# Driver.net
KiCad netlist of a schematic drawn in Altium Designer
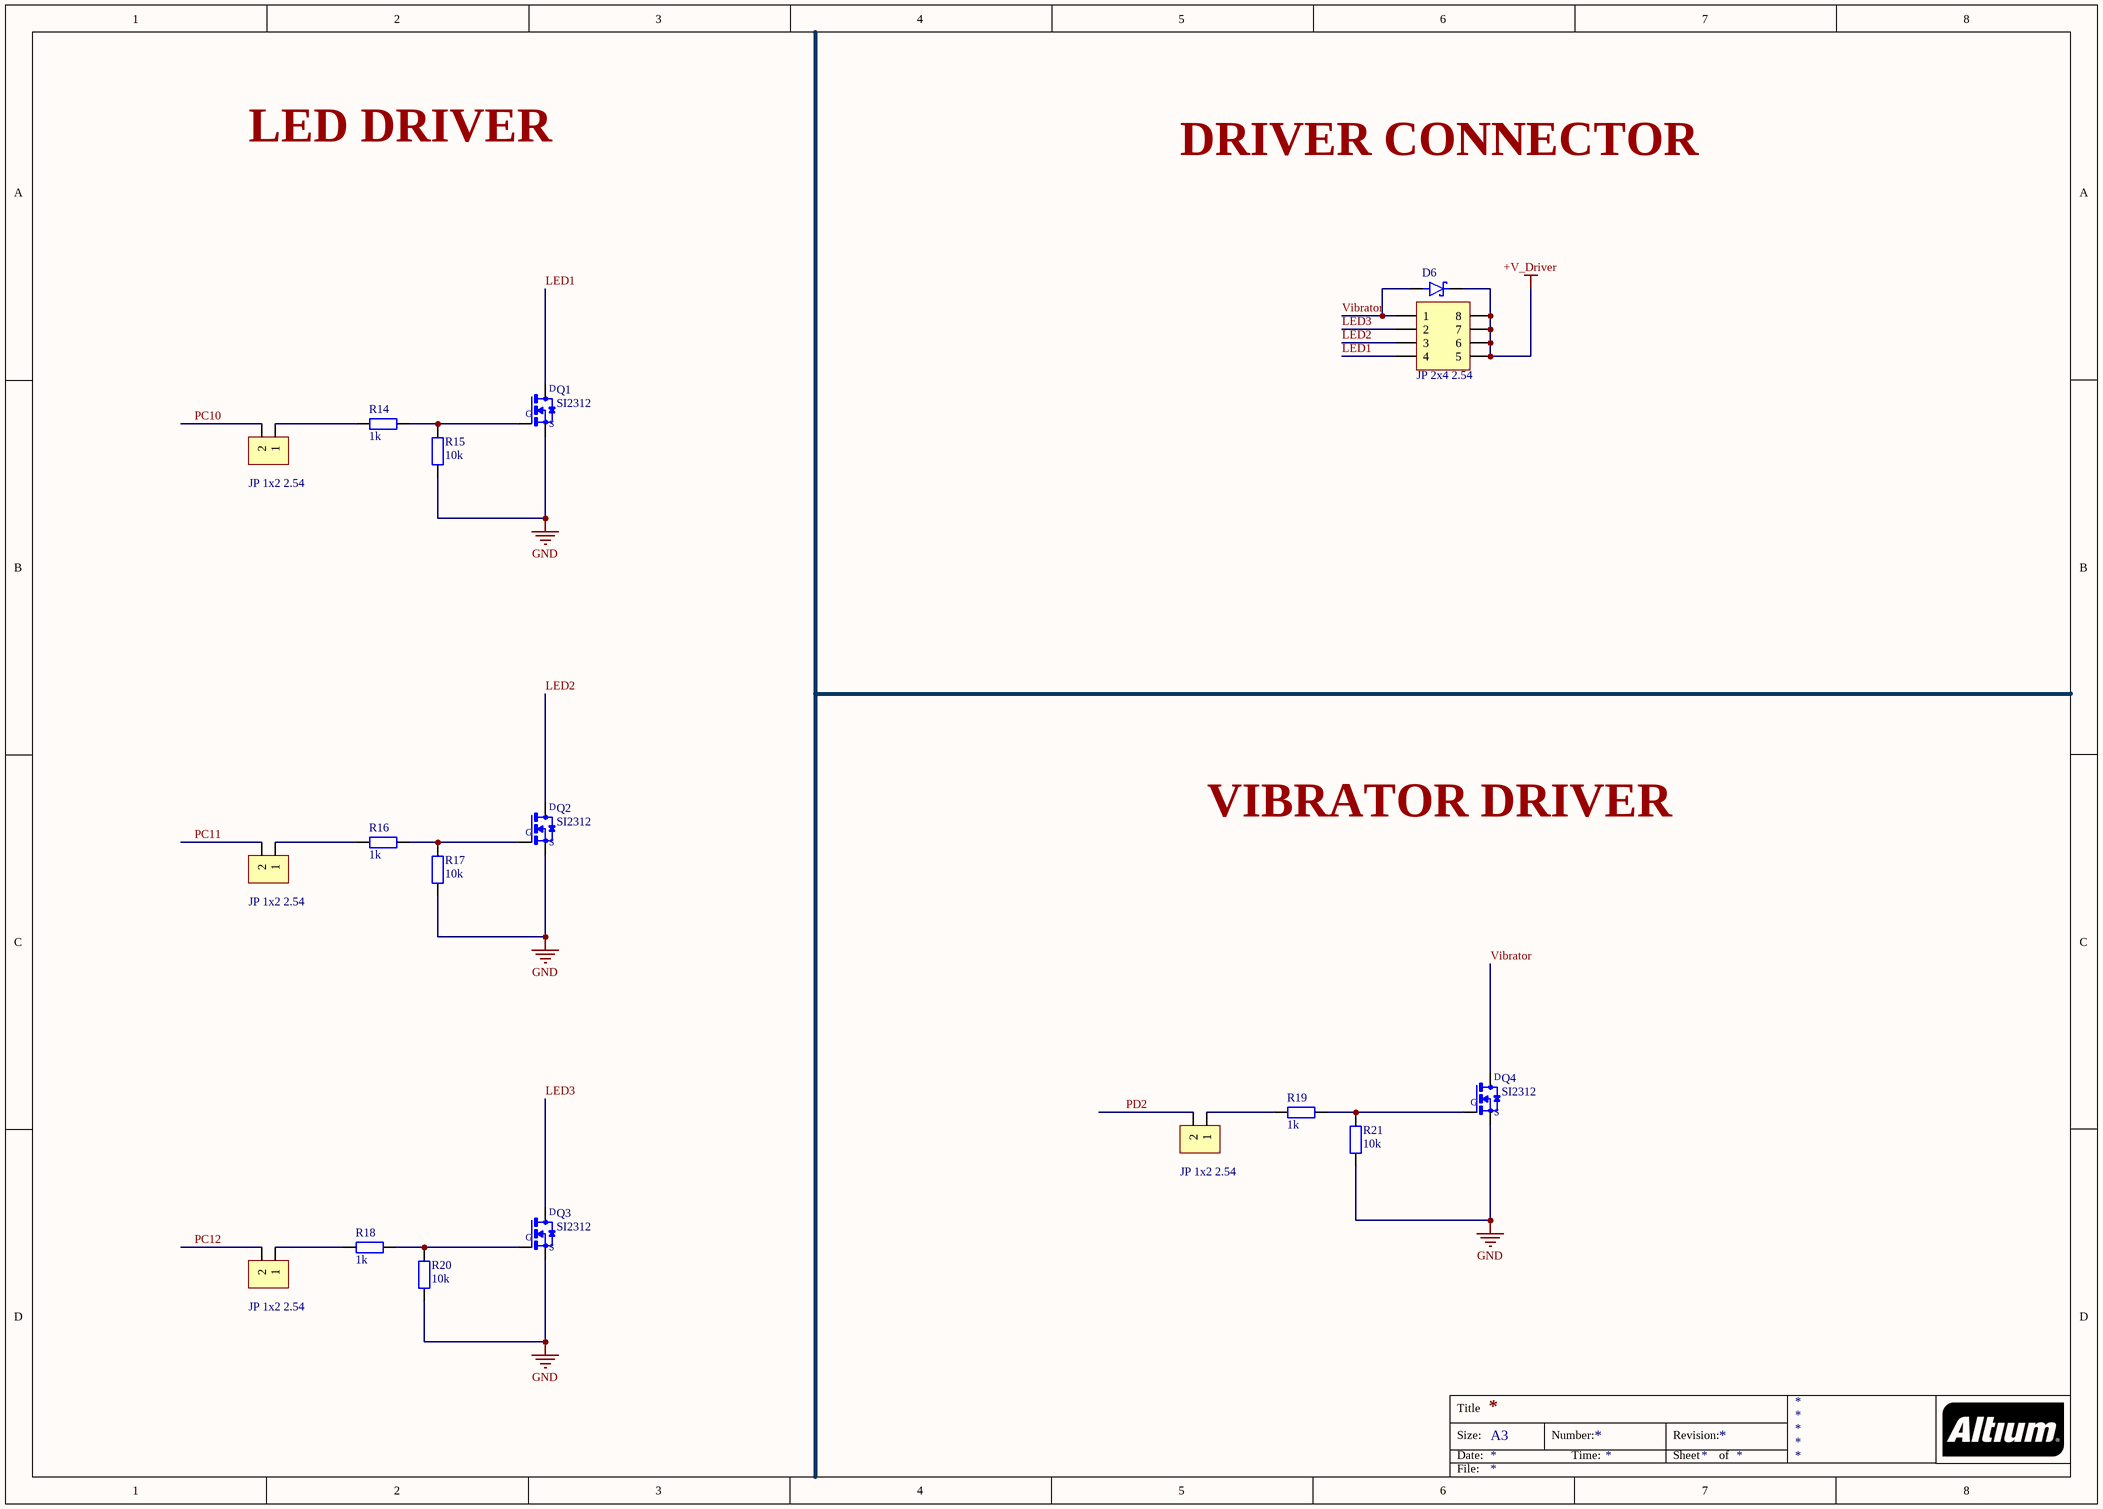
[diagram p0: Driver.SchDoc]

(export (version "E")
  (design (tool "Eeschema 10.0.6"))
  (components
    (comp (ref "D6")
      (value "1N5819HW-7-F")
      (footprint "SOD3715X145N")
      (description "1N5819HW Series 40 V 1 A Surface Mount Schottky Barrier Rectifier - SOD-123")
      (fields (field (name "MF") "{'manufacturer': u'Diodes Inc.'}"))
      (libsource (lib "SnapEDA_Library") (part "1N5819HW-7-F"))
    )
    (comp (ref "Driver1")
      (value "JP 2x4 2.54")
      (footprint "JP 2x4 DT")
      (description "Cắm")
      (libsource (lib "Altium_Lib_by_KhueNguyenCreator") (part "JP 2x4 2.54 Duc Thang"))
    )
    (comp (ref "JP2")
      (value "JP 1x2 2.54")
      (footprint "JP 1x2 DT")
      (description "Cắm")
      (libsource (lib "Altium_Lib_by_KhueNguyenCreator") (part "JP 1x2 2.54 Duc Thang"))
    )
    (comp (ref "JP3")
      (value "JP 1x2 2.54")
      (footprint "JP 1x2 DT")
      (description "Cắm")
      (libsource (lib "Altium_Lib_by_KhueNguyenCreator") (part "JP 1x2 2.54 Duc Thang"))
    )
    (comp (ref "JP4")
      (value "JP 1x2 2.54")
      (footprint "JP 1x2 DT")
      (description "Cắm")
      (libsource (lib "Altium_Lib_by_KhueNguyenCreator") (part "JP 1x2 2.54 Duc Thang"))
    )
    (comp (ref "JP5")
      (value "JP 1x2 2.54")
      (footprint "JP 1x2 DT")
      (description "Cắm")
      (libsource (lib "Altium_Lib_by_KhueNguyenCreator") (part "JP 1x2 2.54 Duc Thang"))
    )
    (comp (ref "Q1")
      (value "SI2312")
      (footprint "SI2312-TP:SOT23")
      (fields
        (field (name "MF") "{'manufacturer': u'Micro Commercial Components'}")
        (field (name "MP") "SI2312-TP")
      )
      (libsource (lib "*") (part "SI2312"))
    )
    (comp (ref "Q2")
      (value "SI2312")
      (footprint "SI2312-TP:SOT23")
      (fields
        (field (name "MF") "{'manufacturer': u'Micro Commercial Components'}")
        (field (name "MP") "SI2312-TP")
      )
      (libsource (lib "*") (part "SI2312"))
    )
    (comp (ref "Q3")
      (value "SI2312")
      (footprint "SI2312-TP:SOT23")
      (fields
        (field (name "MF") "{'manufacturer': u'Micro Commercial Components'}")
        (field (name "MP") "SI2312-TP")
      )
      (libsource (lib "*") (part "SI2312"))
    )
    (comp (ref "Q4")
      (value "SI2312")
      (footprint "SI2312-TP:SOT23")
      (fields
        (field (name "MF") "{'manufacturer': u'Micro Commercial Components'}")
        (field (name "MP") "SI2312-TP")
      )
      (libsource (lib "*") (part "SI2312"))
    )
    (comp (ref "R14")
      (value "1k")
      (footprint "tro smd 0603")
      (description "Dán")
      (libsource (lib "Altium_Lib_by_KhueNguyenCreator") (part "Tro 0603 1% 1k"))
    )
    (comp (ref "R15")
      (value "10k")
      (footprint "tro smd 0603")
      (description "Dán")
      (libsource (lib "Altium_Lib_by_KhueNguyenCreator") (part "Tro 0603 1% 10k"))
    )
    (comp (ref "R16")
      (value "1k")
      (footprint "tro smd 0603")
      (description "Dán")
      (libsource (lib "Altium_Lib_by_KhueNguyenCreator") (part "Tro 0603 1% 1k"))
    )
    (comp (ref "R17")
      (value "10k")
      (footprint "tro smd 0603")
      (description "Dán")
      (libsource (lib "Altium_Lib_by_KhueNguyenCreator") (part "Tro 0603 1% 10k"))
    )
    (comp (ref "R18")
      (value "1k")
      (footprint "tro smd 0603")
      (description "Dán")
      (libsource (lib "Altium_Lib_by_KhueNguyenCreator") (part "Tro 0603 1% 1k"))
    )
    (comp (ref "R19")
      (value "1k")
      (footprint "tro smd 0603")
      (description "Dán")
      (libsource (lib "Altium_Lib_by_KhueNguyenCreator") (part "Tro 0603 1% 1k"))
    )
    (comp (ref "R20")
      (value "10k")
      (footprint "tro smd 0603")
      (description "Dán")
      (libsource (lib "Altium_Lib_by_KhueNguyenCreator") (part "Tro 0603 1% 10k"))
    )
    (comp (ref "R21")
      (value "10k")
      (footprint "tro smd 0603")
      (description "Dán")
      (libsource (lib "Altium_Lib_by_KhueNguyenCreator") (part "Tro 0603 1% 10k"))
    )
  )
  (nets
    (net (code "1") (name "+V_Driver") (class "Default")
      (node (ref "D6") (pin "C") (pinfunction "K_C") (pintype "passive"))
      (node (ref "Driver1") (pin "5") (pinfunction "5_5") (pintype "passive"))
      (node (ref "Driver1") (pin "6") (pinfunction "6_6") (pintype "passive"))
      (node (ref "Driver1") (pin "7") (pinfunction "7_7") (pintype "passive"))
      (node (ref "Driver1") (pin "8") (pinfunction "8_8") (pintype "passive"))
    )
    (net (code "2") (name "/LED1") (class "Default")
      (node (ref "Driver1") (pin "4") (pinfunction "4_4") (pintype "passive"))
      (node (ref "Q1") (pin "3") (pinfunction "D_3") (pintype "passive"))
    )
    (net (code "3") (name "/LED2") (class "Default")
      (node (ref "Driver1") (pin "3") (pinfunction "3_3") (pintype "passive"))
      (node (ref "Q2") (pin "3") (pinfunction "D_3") (pintype "passive"))
    )
    (net (code "4") (name "/LED3") (class "Default")
      (node (ref "Driver1") (pin "2") (pinfunction "2_2") (pintype "passive"))
      (node (ref "Q3") (pin "3") (pinfunction "D_3") (pintype "passive"))
    )
    (net (code "5") (name "/PC10") (class "Default")
      (node (ref "JP2") (pin "2") (pinfunction "2_2") (pintype "passive"))
    )
    (net (code "6") (name "/PC11") (class "Default")
      (node (ref "JP3") (pin "2") (pinfunction "2_2") (pintype "passive"))
    )
    (net (code "7") (name "/PC12") (class "Default")
      (node (ref "JP4") (pin "2") (pinfunction "2_2") (pintype "passive"))
    )
    (net (code "8") (name "/PD2") (class "Default")
      (node (ref "JP5") (pin "2") (pinfunction "2_2") (pintype "passive"))
    )
    (net (code "9") (name "/Vibrator") (class "Default")
      (node (ref "D6") (pin "A") (pinfunction "A_A") (pintype "passive"))
      (node (ref "Driver1") (pin "1") (pinfunction "1_1") (pintype "passive"))
      (node (ref "Q4") (pin "3") (pinfunction "D_3") (pintype "passive"))
    )
    (net (code "10") (name "GND") (class "Default")
      (node (ref "Q1") (pin "2") (pinfunction "S_2") (pintype "passive"))
      (node (ref "Q2") (pin "2") (pinfunction "S_2") (pintype "passive"))
      (node (ref "Q3") (pin "2") (pinfunction "S_2") (pintype "passive"))
      (node (ref "Q4") (pin "2") (pinfunction "S_2") (pintype "passive"))
      (node (ref "R15") (pin "1") (pinfunction "1_1") (pintype "passive"))
      (node (ref "R17") (pin "1") (pinfunction "1_1") (pintype "passive"))
      (node (ref "R20") (pin "1") (pinfunction "1_1") (pintype "passive"))
      (node (ref "R21") (pin "1") (pinfunction "1_1") (pintype "passive"))
    )
    (net (code "11") (name "Net-(JP2-Pad1)") (class "Default")
      (node (ref "JP2") (pin "1") (pinfunction "1_1") (pintype "passive"))
      (node (ref "R14") (pin "1") (pinfunction "1_1") (pintype "passive"))
    )
    (net (code "12") (name "Net-(JP3-Pad1)") (class "Default")
      (node (ref "JP3") (pin "1") (pinfunction "1_1") (pintype "passive"))
      (node (ref "R16") (pin "1") (pinfunction "1_1") (pintype "passive"))
    )
    (net (code "13") (name "Net-(JP4-Pad1)") (class "Default")
      (node (ref "JP4") (pin "1") (pinfunction "1_1") (pintype "passive"))
      (node (ref "R18") (pin "1") (pinfunction "1_1") (pintype "passive"))
    )
    (net (code "14") (name "Net-(JP5-Pad1)") (class "Default")
      (node (ref "JP5") (pin "1") (pinfunction "1_1") (pintype "passive"))
      (node (ref "R19") (pin "1") (pinfunction "1_1") (pintype "passive"))
    )
    (net (code "15") (name "Net-(Q1-G)") (class "Default")
      (node (ref "Q1") (pin "1") (pinfunction "G_1") (pintype "passive"))
      (node (ref "R14") (pin "2") (pinfunction "2_2") (pintype "passive"))
      (node (ref "R15") (pin "2") (pinfunction "2_2") (pintype "passive"))
    )
    (net (code "16") (name "Net-(Q2-G)") (class "Default")
      (node (ref "Q2") (pin "1") (pinfunction "G_1") (pintype "passive"))
      (node (ref "R16") (pin "2") (pinfunction "2_2") (pintype "passive"))
      (node (ref "R17") (pin "2") (pinfunction "2_2") (pintype "passive"))
    )
    (net (code "17") (name "Net-(Q3-G)") (class "Default")
      (node (ref "Q3") (pin "1") (pinfunction "G_1") (pintype "passive"))
      (node (ref "R18") (pin "2") (pinfunction "2_2") (pintype "passive"))
      (node (ref "R20") (pin "2") (pinfunction "2_2") (pintype "passive"))
    )
    (net (code "18") (name "Net-(Q4-G)") (class "Default")
      (node (ref "Q4") (pin "1") (pinfunction "G_1") (pintype "passive"))
      (node (ref "R19") (pin "2") (pinfunction "2_2") (pintype "passive"))
      (node (ref "R21") (pin "2") (pinfunction "2_2") (pintype "passive"))
    )
  )
)
